# Walletv3.net
KiCad netlist of a schematic drawn in EAGLE
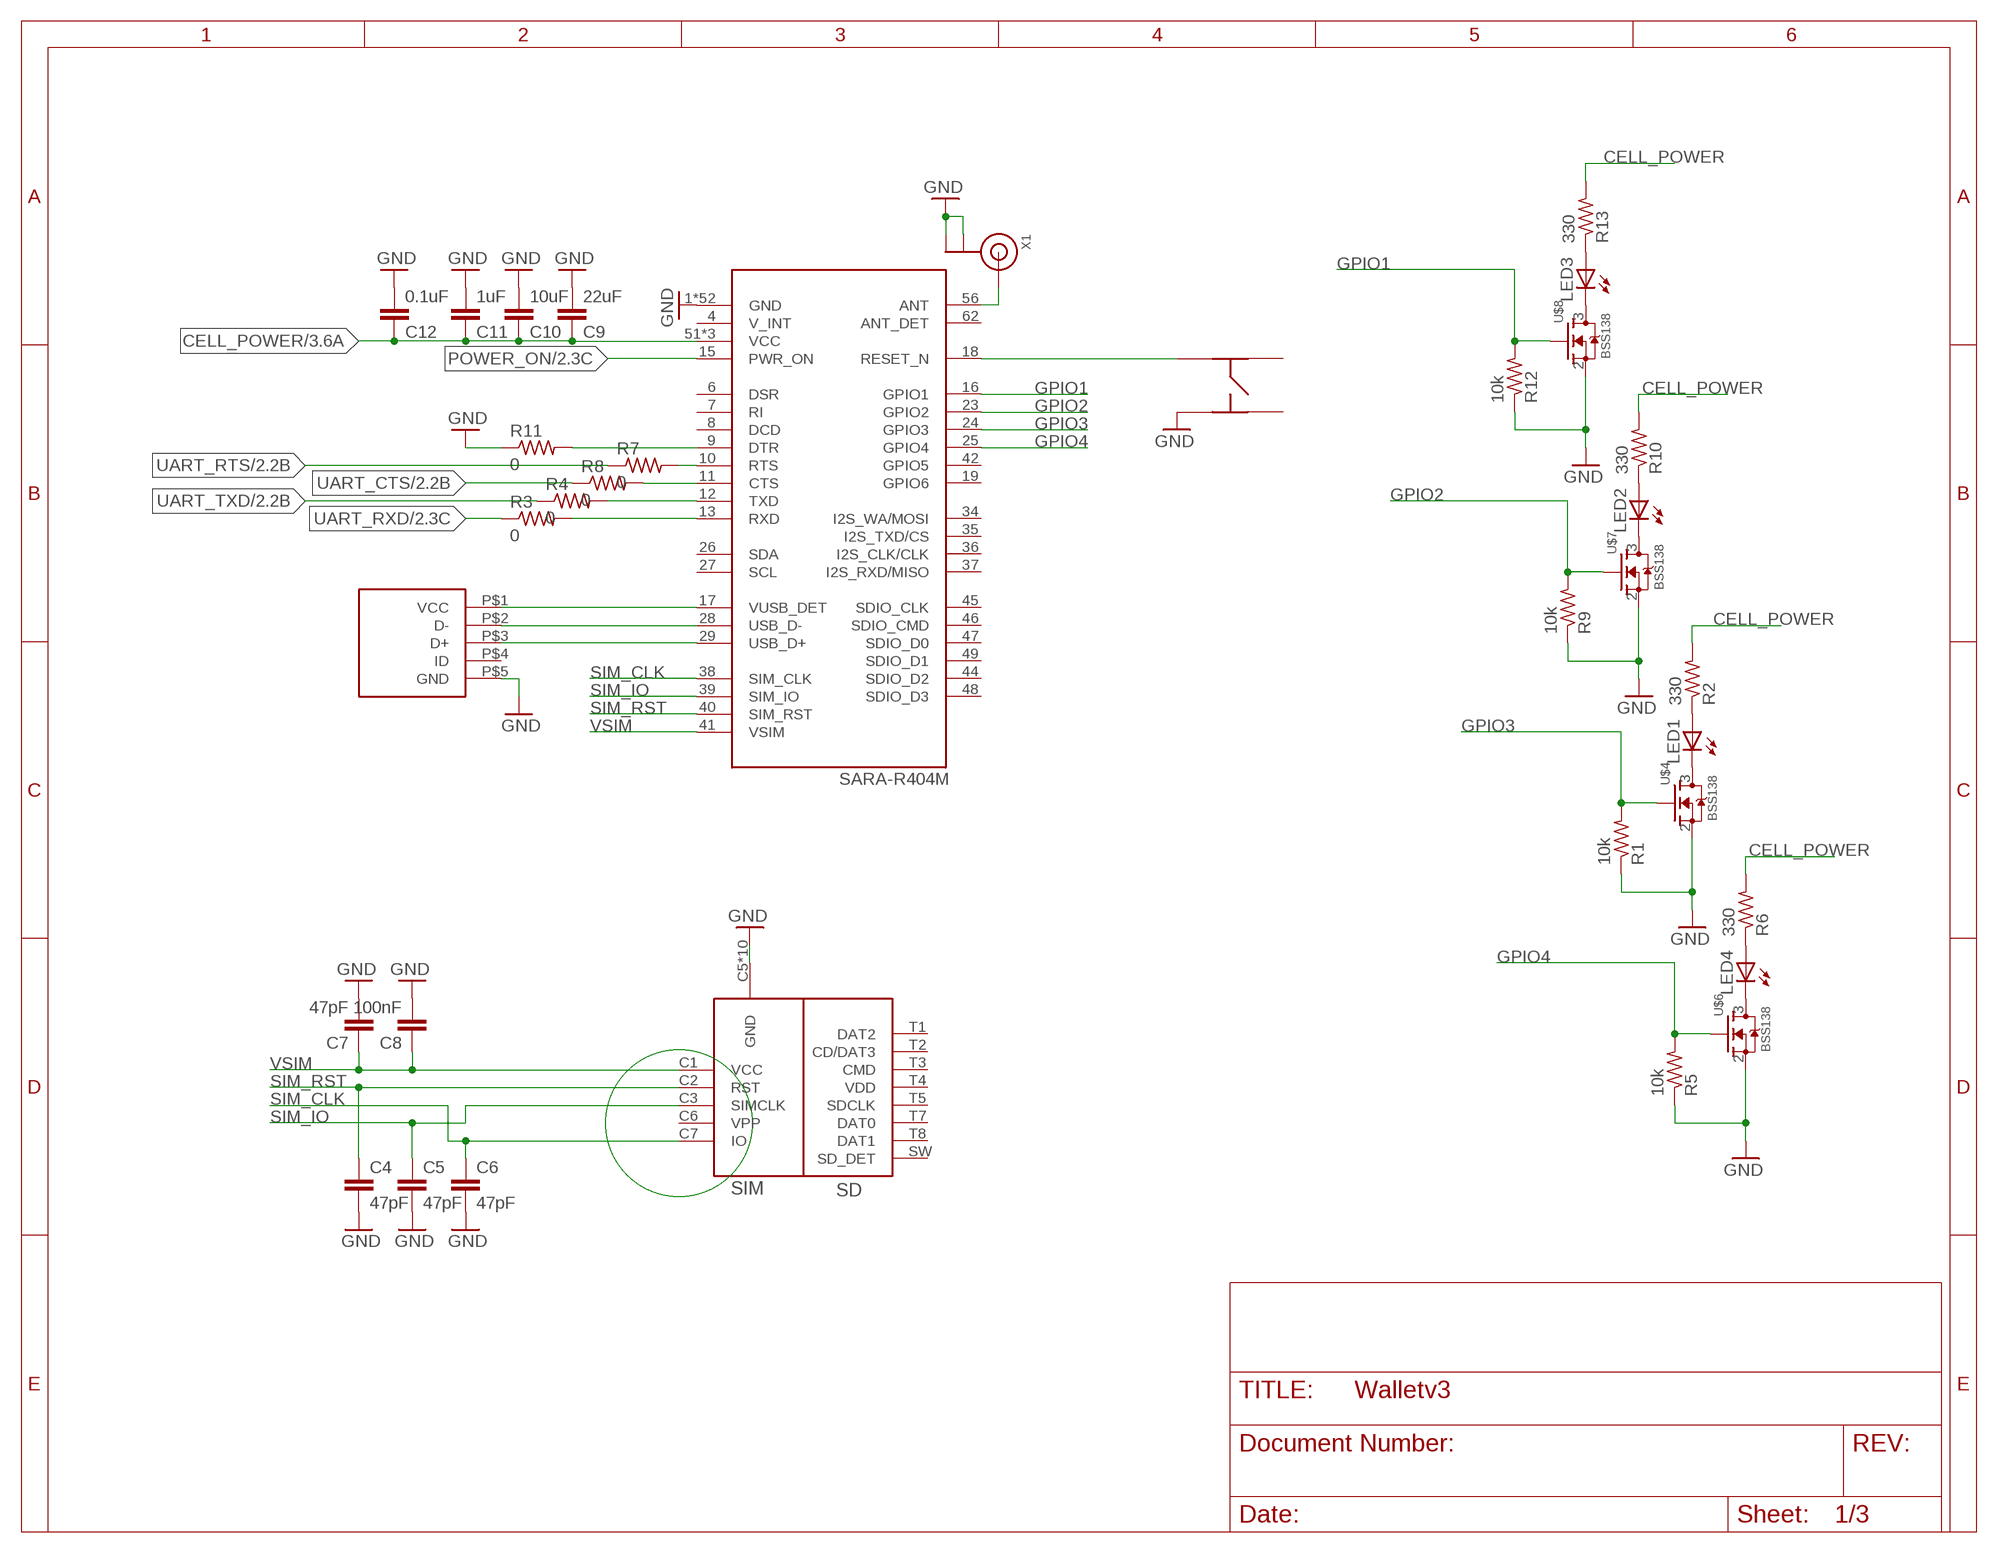
[diagram p0: schematic, sheet 1]
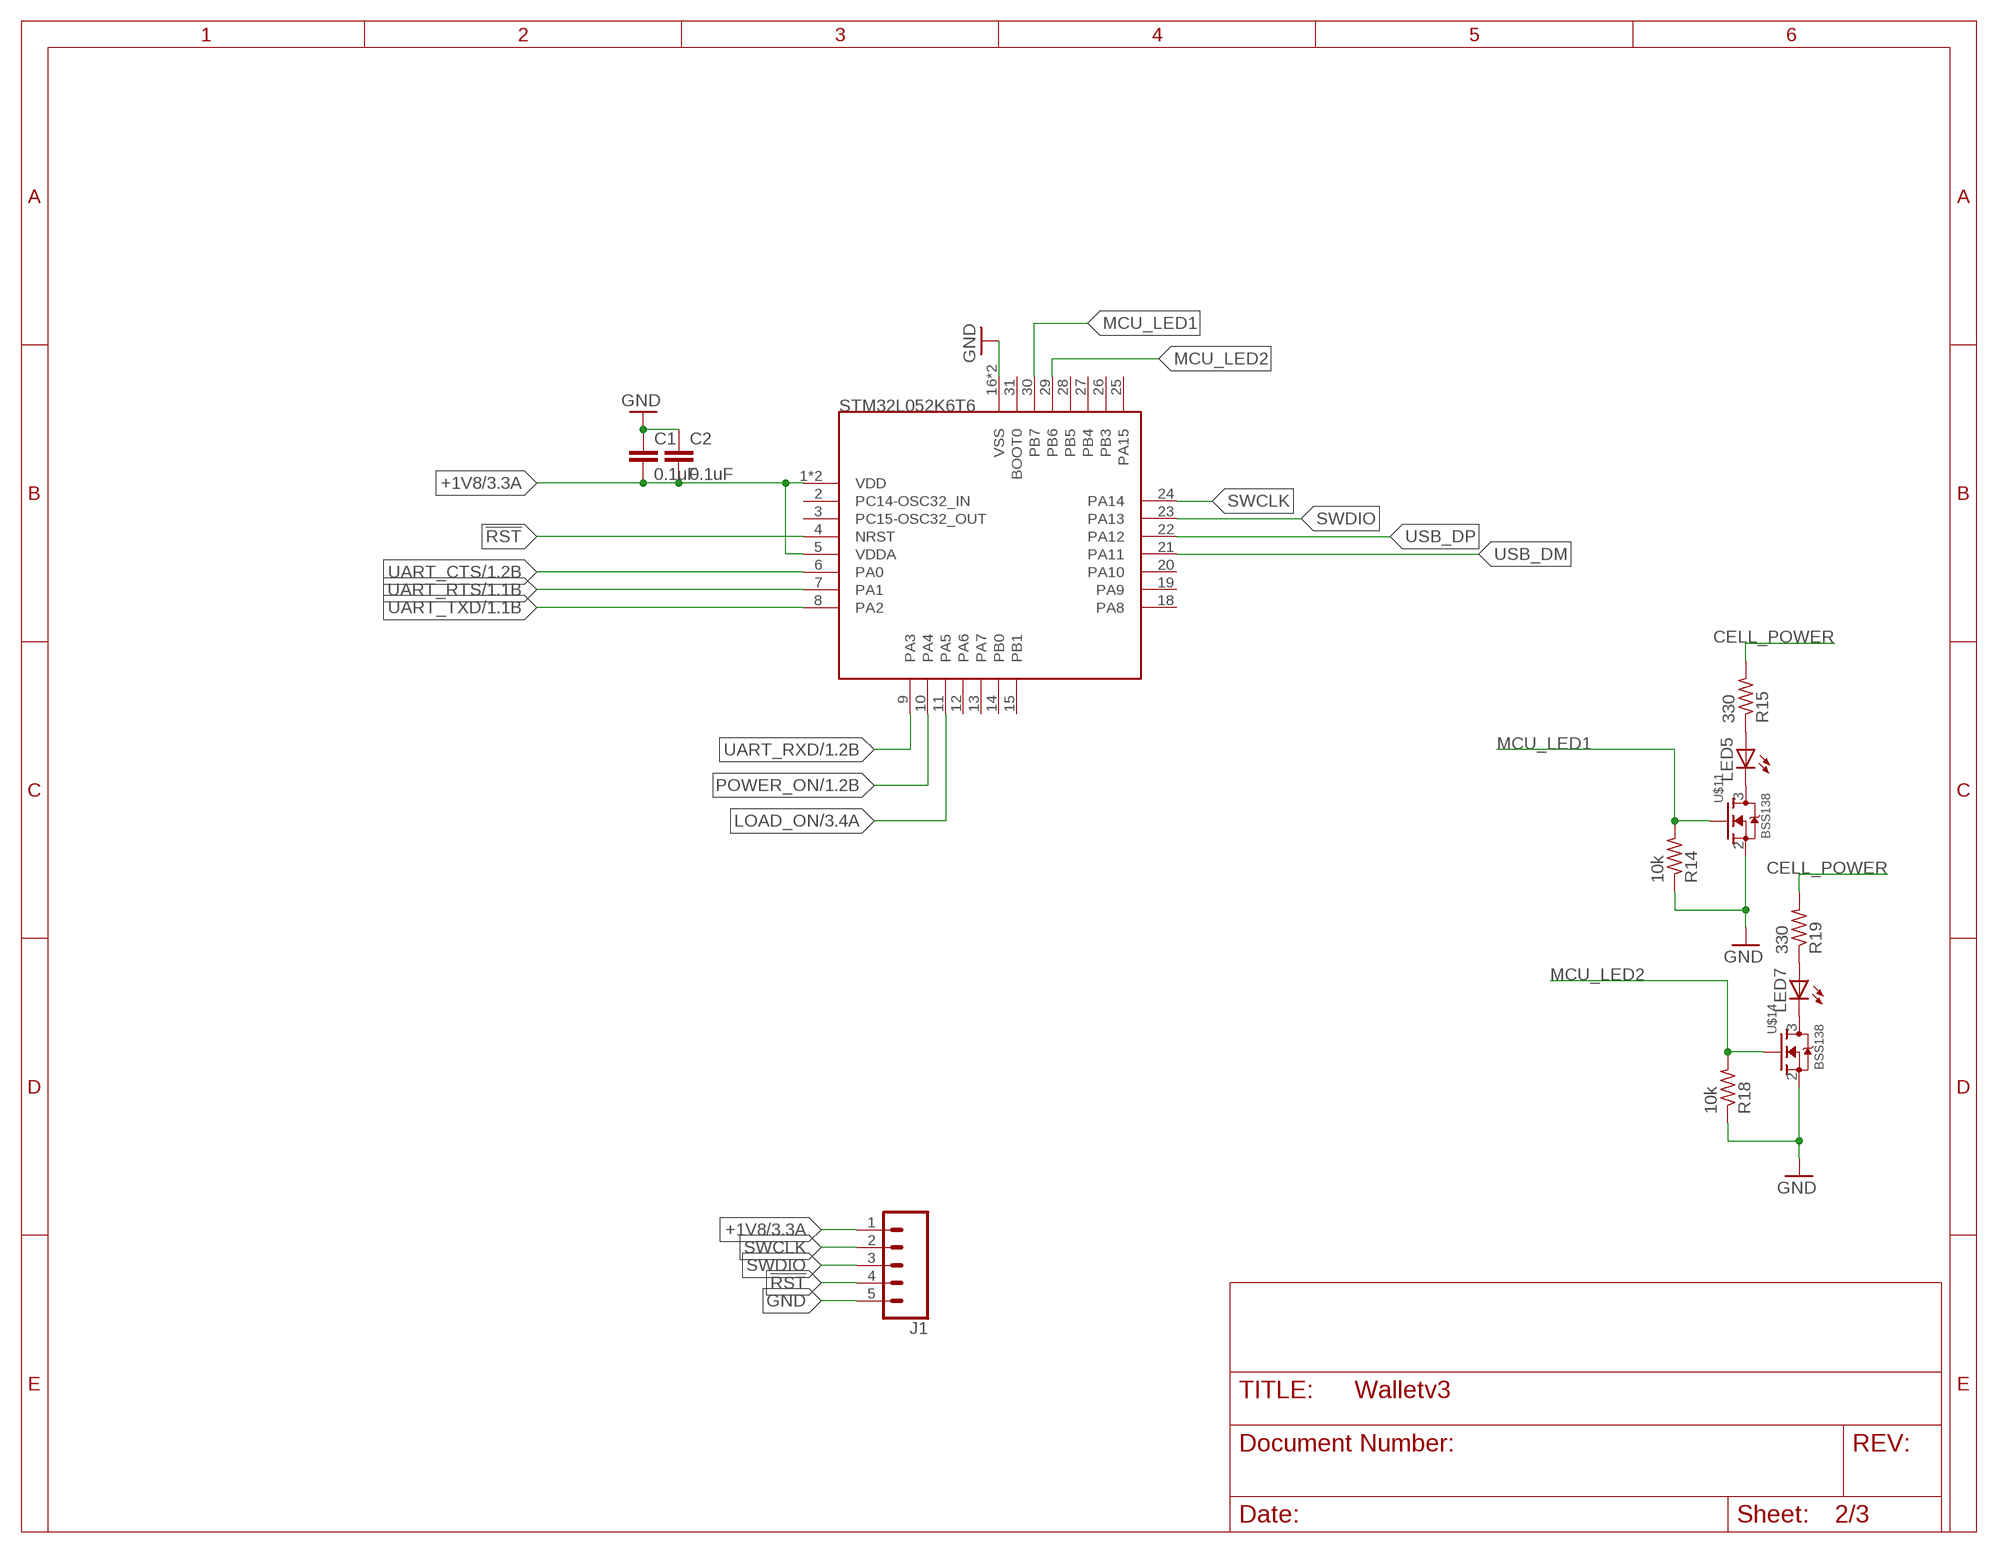
[diagram p1: schematic, sheet 2]
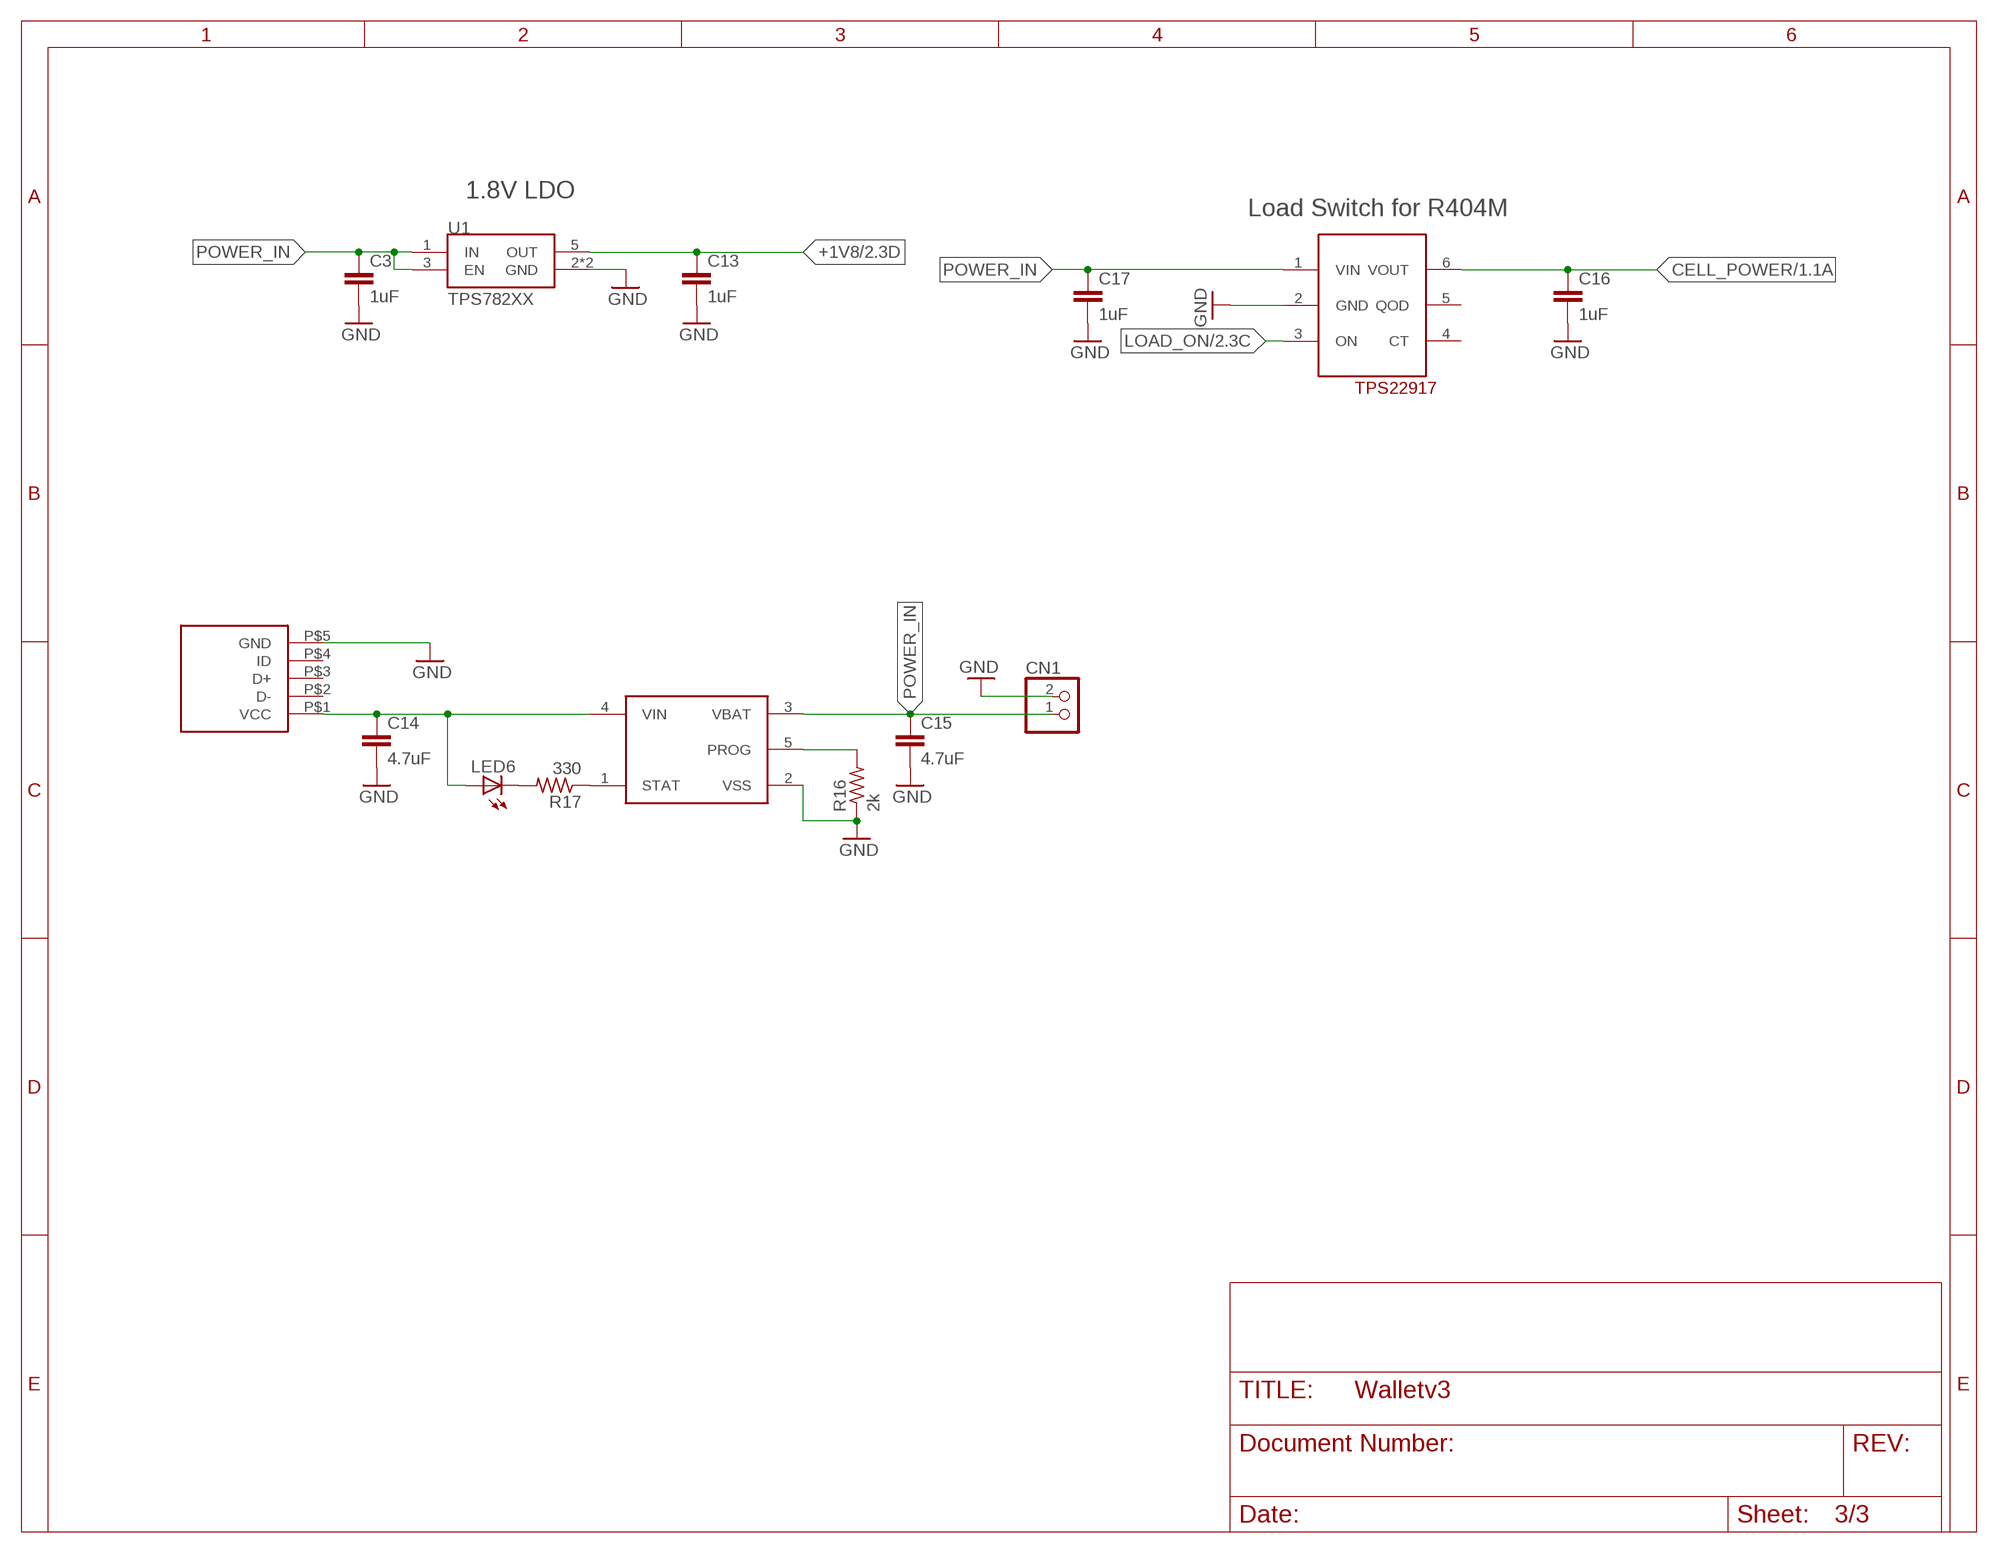
[diagram p2: schematic, sheet 3]

(export (version "E")
  (design (tool "Eeschema 10.0.6"))
  (components
    (comp (ref "C4")
      (value "47pF")
      (footprint "eagle-import:C0402")
      (libsource (lib "eagle-import") (part "C-EUC0402"))
    )
    (comp (ref "C5")
      (value "47pF")
      (footprint "eagle-import:C0402")
      (libsource (lib "eagle-import") (part "C-EUC0402"))
    )
    (comp (ref "C6")
      (value "47pF")
      (footprint "eagle-import:C0402")
      (libsource (lib "eagle-import") (part "C-EUC0402"))
    )
    (comp (ref "C7")
      (value "47pF")
      (footprint "eagle-import:C0402")
      (libsource (lib "eagle-import") (part "C-EUC0402"))
    )
    (comp (ref "C8")
      (value "100nF")
      (footprint "eagle-import:C0402")
      (libsource (lib "eagle-import") (part "C-EUC0402"))
    )
    (comp (ref "C9")
      (value "22uF")
      (footprint "eagle-import:C0805")
      (libsource (lib "eagle-import") (part "C-EUC0805"))
    )
    (comp (ref "C10")
      (value "10uF")
      (footprint "eagle-import:C0603")
      (libsource (lib "eagle-import") (part "C-EUC0603"))
    )
    (comp (ref "C11")
      (value "1uF")
      (footprint "eagle-import:C0402")
      (libsource (lib "eagle-import") (part "C-EUC0402"))
    )
    (comp (ref "C12")
      (value "0.1uF")
      (footprint "eagle-import:C0402")
      (libsource (lib "eagle-import") (part "C-EUC0402"))
    )
    (comp (ref "LED1")
      (value "LEDCHIPLED_0603")
      (footprint "eagle-import:CHIPLED_0603")
      (libsource (lib "eagle-import") (part "LEDCHIPLED_0603"))
    )
    (comp (ref "LED2")
      (value "LEDCHIPLED_0603")
      (footprint "eagle-import:CHIPLED_0603")
      (libsource (lib "eagle-import") (part "LEDCHIPLED_0603"))
    )
    (comp (ref "LED3")
      (value "LEDCHIPLED_0603")
      (footprint "eagle-import:CHIPLED_0603")
      (libsource (lib "eagle-import") (part "LEDCHIPLED_0603"))
    )
    (comp (ref "LED4")
      (value "LEDCHIPLED_0603")
      (footprint "eagle-import:CHIPLED_0603")
      (libsource (lib "eagle-import") (part "LEDCHIPLED_0603"))
    )
    (comp (ref "R1")
      (value "10k")
      (footprint "eagle-import:R0402")
      (libsource (lib "eagle-import") (part "R-US_R0402"))
    )
    (comp (ref "R2")
      (value "330")
      (footprint "eagle-import:R0402")
      (libsource (lib "eagle-import") (part "R-US_R0402"))
    )
    (comp (ref "R3")
      (value "0")
      (footprint "eagle-import:R0402")
      (libsource (lib "eagle-import") (part "R-US_R0402"))
    )
    (comp (ref "R4")
      (value "0")
      (footprint "eagle-import:R0402")
      (libsource (lib "eagle-import") (part "R-US_R0402"))
    )
    (comp (ref "R5")
      (value "10k")
      (footprint "eagle-import:R0402")
      (libsource (lib "eagle-import") (part "R-US_R0402"))
    )
    (comp (ref "R6")
      (value "330")
      (footprint "eagle-import:R0402")
      (libsource (lib "eagle-import") (part "R-US_R0402"))
    )
    (comp (ref "R7")
      (value "0")
      (footprint "eagle-import:R0402")
      (libsource (lib "eagle-import") (part "R-US_R0402"))
    )
    (comp (ref "R8")
      (value "0")
      (footprint "eagle-import:R0402")
      (libsource (lib "eagle-import") (part "R-US_R0402"))
    )
    (comp (ref "R9")
      (value "10k")
      (footprint "eagle-import:R0402")
      (libsource (lib "eagle-import") (part "R-US_R0402"))
    )
    (comp (ref "R10")
      (value "330")
      (footprint "eagle-import:R0402")
      (libsource (lib "eagle-import") (part "R-US_R0402"))
    )
    (comp (ref "R11")
      (value "0")
      (footprint "eagle-import:R0402")
      (libsource (lib "eagle-import") (part "R-US_R0402"))
    )
    (comp (ref "R12")
      (value "10k")
      (footprint "eagle-import:R0402")
      (libsource (lib "eagle-import") (part "R-US_R0402"))
    )
    (comp (ref "R13")
      (value "330")
      (footprint "eagle-import:R0402")
      (libsource (lib "eagle-import") (part "R-US_R0402"))
    )
    (comp (ref "U$2")
      (value "SIM_SD_MOLEX")
      (footprint "eagle-import:SIM_SD_MOLEX")
      (libsource (lib "eagle-import") (part "SIM_SD_MOLEX"))
    )
    (comp (ref "U$3")
      (value "SARA-R404M")
      (footprint "eagle-import:SARA-R404M")
      (libsource (lib "eagle-import") (part "SARA-R404M"))
    )
    (comp (ref "U$4")
      (value "BSS138")
      (footprint "eagle-import:SOT23-3")
      (libsource (lib "eagle-import") (part "BSS138"))
    )
    (comp (ref "U$5")
      (value "MICRO_USB")
      (footprint "eagle-import:MOLEX_USB")
      (libsource (lib "eagle-import") (part "Charles_104873_MICRO_USB"))
    )
    (comp (ref "U$6")
      (value "BSS138")
      (footprint "eagle-import:SOT23-3")
      (libsource (lib "eagle-import") (part "BSS138"))
    )
    (comp (ref "U$7")
      (value "BSS138")
      (footprint "eagle-import:SOT23-3")
      (libsource (lib "eagle-import") (part "BSS138"))
    )
    (comp (ref "U$8")
      (value "BSS138")
      (footprint "eagle-import:SOT23-3")
      (libsource (lib "eagle-import") (part "BSS138"))
    )
    (comp (ref "U$9")
      (value "KMR731NG")
      (footprint "eagle-import:KMR731NG")
      (libsource (lib "eagle-import") (part "KMR731NG"))
    )
    (comp (ref "X1")
      (value "ANTENNA_U.FL")
      (footprint "eagle-import:U.FL")
      (libsource (lib "eagle-import") (part "ANTENNA_U.FL"))
    )
    (comp (ref "C1")
      (value "0.1uF")
      (footprint "eagle-import:C0402")
      (libsource (lib "eagle-import") (part "C-EUC0402"))
    )
    (comp (ref "C2")
      (value "0.1uF")
      (footprint "eagle-import:C0402")
      (libsource (lib "eagle-import") (part "C-EUC0402"))
    )
    (comp (ref "J1")
      (value "CONN_05")
      (footprint "eagle-import:1X05")
      (libsource (lib "eagle-import") (part "CONN_05"))
    )
    (comp (ref "LED5")
      (value "LEDCHIPLED_0603")
      (footprint "eagle-import:CHIPLED_0603")
      (libsource (lib "eagle-import") (part "LEDCHIPLED_0603"))
    )
    (comp (ref "LED7")
      (value "LEDCHIPLED_0603")
      (footprint "eagle-import:CHIPLED_0603")
      (libsource (lib "eagle-import") (part "LEDCHIPLED_0603"))
    )
    (comp (ref "R14")
      (value "10k")
      (footprint "eagle-import:R0402")
      (libsource (lib "eagle-import") (part "R-US_R0402"))
    )
    (comp (ref "R15")
      (value "330")
      (footprint "eagle-import:R0402")
      (libsource (lib "eagle-import") (part "R-US_R0402"))
    )
    (comp (ref "R18")
      (value "10k")
      (footprint "eagle-import:R0402")
      (libsource (lib "eagle-import") (part "R-US_R0402"))
    )
    (comp (ref "R19")
      (value "330")
      (footprint "eagle-import:R0402")
      (libsource (lib "eagle-import") (part "R-US_R0402"))
    )
    (comp (ref "U$1")
      (value "STM32L052K6T6LQFP32-7X7")
      (footprint "eagle-import:QFP80P900X900X160-32")
      (libsource (lib "eagle-import") (part "STM32L052K6T6LQFP32-7X7"))
    )
    (comp (ref "U$11")
      (value "BSS138")
      (footprint "eagle-import:SOT23-3")
      (libsource (lib "eagle-import") (part "BSS138"))
    )
    (comp (ref "U$14")
      (value "BSS138")
      (footprint "eagle-import:SOT23-3")
      (libsource (lib "eagle-import") (part "BSS138"))
    )
    (comp (ref "C3")
      (value "1uF")
      (footprint "eagle-import:C0402")
      (libsource (lib "eagle-import") (part "C-EUC0402"))
    )
    (comp (ref "C13")
      (value "1uF")
      (footprint "eagle-import:C0402")
      (libsource (lib "eagle-import") (part "C-EUC0402"))
    )
    (comp (ref "C14")
      (value "4.7uF")
      (footprint "eagle-import:C0603")
      (libsource (lib "eagle-import") (part "C-EUC0603"))
    )
    (comp (ref "C15")
      (value "4.7uF")
      (footprint "eagle-import:C0603")
      (libsource (lib "eagle-import") (part "C-EUC0603"))
    )
    (comp (ref "C16")
      (value "1uF")
      (footprint "eagle-import:C0402")
      (libsource (lib "eagle-import") (part "C-EUC0402"))
    )
    (comp (ref "C17")
      (value "1uF")
      (footprint "eagle-import:C0402")
      (libsource (lib "eagle-import") (part "C-EUC0402"))
    )
    (comp (ref "CN1")
      (value "JST_2PIN-SMT-RA")
      (footprint "eagle-import:JST-PH-2-SMT-RA")
      (libsource (lib "eagle-import") (part "JST_2PIN-SMT-RA"))
    )
    (comp (ref "LED6")
      (value "LEDCHIP-LED0603")
      (footprint "eagle-import:CHIP-LED0603")
      (libsource (lib "eagle-import") (part "LEDCHIP-LED0603"))
    )
    (comp (ref "R16")
      (value "2k")
      (footprint "eagle-import:R0402")
      (libsource (lib "eagle-import") (part "R-US_R0402"))
    )
    (comp (ref "R17")
      (value "330")
      (footprint "eagle-import:R0402")
      (libsource (lib "eagle-import") (part "R-US_R0402"))
    )
    (comp (ref "U$10")
      (value "TPS22917")
      (footprint "eagle-import:SOT23-6")
      (libsource (lib "eagle-import") (part "TPS22917"))
    )
    (comp (ref "U$12")
      (value "MICRO_USB")
      (footprint "eagle-import:MOLEX_USB")
      (libsource (lib "eagle-import") (part "MICRO_USB"))
    )
    (comp (ref "U$13")
      (value "MCP73831")
      (footprint "eagle-import:SOT23-5L")
      (libsource (lib "eagle-import") (part "MCP73831"))
    )
    (comp (ref "U1")
      (value "TPS782XX")
      (footprint "eagle-import:SOT23-5L")
      (libsource (lib "eagle-import") (part "TPS782XX"))
    )
  )
  (nets
    (net (code "1") (name "+1V8") (class "Default")
      (node (ref "C1") (pin "2") (pinfunction "2_2") (pintype "passive"))
      (node (ref "C13") (pin "1") (pinfunction "1_1") (pintype "passive"))
      (node (ref "C2") (pin "2") (pinfunction "2_2") (pintype "passive"))
      (node (ref "J1") (pin "1") (pinfunction "1_1") (pintype "passive"))
      (node (ref "U$1") (pin "1") (pinfunction "VDD_1") (pintype "bidirectional"))
      (node (ref "U$1") (pin "17") (pinfunction "VDD_17") (pintype "bidirectional"))
      (node (ref "U$1") (pin "5") (pinfunction "VDDA_5") (pintype "bidirectional"))
      (node (ref "U1") (pin "5") (pinfunction "OUT_5") (pintype "bidirectional"))
    )
    (net (code "2") (name "CELL_POWER") (class "Default")
      (node (ref "C10") (pin "1") (pinfunction "1_1") (pintype "passive"))
      (node (ref "C11") (pin "1") (pinfunction "1_1") (pintype "passive"))
      (node (ref "C12") (pin "1") (pinfunction "1_1") (pintype "passive"))
      (node (ref "C16") (pin "1") (pinfunction "1_1") (pintype "passive"))
      (node (ref "C9") (pin "1") (pinfunction "1_1") (pintype "passive"))
      (node (ref "R10") (pin "2") (pinfunction "2_2") (pintype "passive"))
      (node (ref "R13") (pin "2") (pinfunction "2_2") (pintype "passive"))
      (node (ref "R15") (pin "2") (pinfunction "2_2") (pintype "passive"))
      (node (ref "R19") (pin "2") (pinfunction "2_2") (pintype "passive"))
      (node (ref "R2") (pin "2") (pinfunction "2_2") (pintype "passive"))
      (node (ref "R6") (pin "2") (pinfunction "2_2") (pintype "passive"))
      (node (ref "U$10") (pin "6") (pinfunction "VOUT_6") (pintype "bidirectional"))
      (node (ref "U$3") (pin "51") (pinfunction "VCC_51") (pintype "bidirectional"))
      (node (ref "U$3") (pin "52") (pinfunction "VCC_52") (pintype "bidirectional"))
      (node (ref "U$3") (pin "53") (pinfunction "VCC_53") (pintype "bidirectional"))
    )
    (net (code "3") (name "GND") (class "Default")
      (node (ref "C1") (pin "1") (pinfunction "1_1") (pintype "passive"))
      (node (ref "C10") (pin "2") (pinfunction "2_2") (pintype "passive"))
      (node (ref "C11") (pin "2") (pinfunction "2_2") (pintype "passive"))
      (node (ref "C12") (pin "2") (pinfunction "2_2") (pintype "passive"))
      (node (ref "C13") (pin "2") (pinfunction "2_2") (pintype "passive"))
      (node (ref "C14") (pin "2") (pinfunction "2_2") (pintype "passive"))
      (node (ref "C15") (pin "2") (pinfunction "2_2") (pintype "passive"))
      (node (ref "C16") (pin "2") (pinfunction "2_2") (pintype "passive"))
      (node (ref "C17") (pin "2") (pinfunction "2_2") (pintype "passive"))
      (node (ref "C2") (pin "1") (pinfunction "1_1") (pintype "passive"))
      (node (ref "C3") (pin "2") (pinfunction "2_2") (pintype "passive"))
      (node (ref "C4") (pin "2") (pinfunction "2_2") (pintype "passive"))
      (node (ref "C5") (pin "2") (pinfunction "2_2") (pintype "passive"))
      (node (ref "C6") (pin "2") (pinfunction "2_2") (pintype "passive"))
      (node (ref "C7") (pin "2") (pinfunction "2_2") (pintype "passive"))
      (node (ref "C8") (pin "2") (pinfunction "2_2") (pintype "passive"))
      (node (ref "C9") (pin "2") (pinfunction "2_2") (pintype "passive"))
      (node (ref "CN1") (pin "2") (pinfunction "1_2") (pintype "passive"))
      (node (ref "J1") (pin "5") (pinfunction "5_5") (pintype "passive"))
      (node (ref "R1") (pin "1") (pinfunction "1_1") (pintype "passive"))
      (node (ref "R11") (pin "1") (pinfunction "1_1") (pintype "passive"))
      (node (ref "R12") (pin "1") (pinfunction "1_1") (pintype "passive"))
      (node (ref "R14") (pin "1") (pinfunction "1_1") (pintype "passive"))
      (node (ref "R16") (pin "1") (pinfunction "1_1") (pintype "passive"))
      (node (ref "R18") (pin "1") (pinfunction "1_1") (pintype "passive"))
      (node (ref "R5") (pin "1") (pinfunction "1_1") (pintype "passive"))
      (node (ref "R9") (pin "1") (pinfunction "1_1") (pintype "passive"))
      (node (ref "U$1") (pin "16") (pinfunction "VSS_16") (pintype "bidirectional"))
      (node (ref "U$1") (pin "32") (pinfunction "VSS_32") (pintype "bidirectional"))
      (node (ref "U$10") (pin "2") (pinfunction "GND_2") (pintype "bidirectional"))
      (node (ref "U$11") (pin "2") (pinfunction "S_2") (pintype "bidirectional"))
      (node (ref "U$12") (pin "P$5") (pinfunction "GND_P$5") (pintype "bidirectional"))
      (node (ref "U$13") (pin "2") (pinfunction "VSS_2") (pintype "bidirectional"))
      (node (ref "U$14") (pin "2") (pinfunction "S_2") (pintype "bidirectional"))
      (node (ref "U$2") (pin "C5") (pinfunction "GND_C5") (pintype "bidirectional"))
      (node (ref "U$2") (pin "G1") (pinfunction "GND_G1") (pintype "bidirectional"))
      (node (ref "U$2") (pin "G2") (pinfunction "GND_G2") (pintype "bidirectional"))
      (node (ref "U$2") (pin "G3") (pinfunction "GND_G3") (pintype "bidirectional"))
      (node (ref "U$2") (pin "G4") (pinfunction "GND_G4") (pintype "bidirectional"))
      (node (ref "U$2") (pin "G5") (pinfunction "GND_G5") (pintype "bidirectional"))
      (node (ref "U$2") (pin "G6") (pinfunction "GND_G6") (pintype "bidirectional"))
      (node (ref "U$2") (pin "G7") (pinfunction "GND_G7") (pintype "bidirectional"))
      (node (ref "U$2") (pin "G8") (pinfunction "GND_G8") (pintype "bidirectional"))
      (node (ref "U$2") (pin "T6") (pinfunction "GND_T6") (pintype "bidirectional"))
      (node (ref "U$3") (pin "1") (pinfunction "GND_1") (pintype "bidirectional"))
      (node (ref "U$3") (pin "14") (pinfunction "GND_14") (pintype "bidirectional"))
      (node (ref "U$3") (pin "20") (pinfunction "GND_20") (pintype "bidirectional"))
      (node (ref "U$3") (pin "21") (pinfunction "GND_21") (pintype "bidirectional"))
      (node (ref "U$3") (pin "22") (pinfunction "GND_22") (pintype "bidirectional"))
      (node (ref "U$3") (pin "3") (pinfunction "GND_3") (pintype "bidirectional"))
      (node (ref "U$3") (pin "30") (pinfunction "GND_30") (pintype "bidirectional"))
      (node (ref "U$3") (pin "32") (pinfunction "GND_32") (pintype "bidirectional"))
      (node (ref "U$3") (pin "43") (pinfunction "GND_43") (pintype "bidirectional"))
      (node (ref "U$3") (pin "5") (pinfunction "GND_5") (pintype "bidirectional"))
      (node (ref "U$3") (pin "50") (pinfunction "GND_50") (pintype "bidirectional"))
      (node (ref "U$3") (pin "54") (pinfunction "GND_54") (pintype "bidirectional"))
      (node (ref "U$3") (pin "55") (pinfunction "GND_55") (pintype "bidirectional"))
      (node (ref "U$3") (pin "57") (pinfunction "GND_57") (pintype "bidirectional"))
      (node (ref "U$3") (pin "58") (pinfunction "GND_58") (pintype "bidirectional"))
      (node (ref "U$3") (pin "59") (pinfunction "GND_59") (pintype "bidirectional"))
      (node (ref "U$3") (pin "60") (pinfunction "GND_60") (pintype "bidirectional"))
      (node (ref "U$3") (pin "61") (pinfunction "GND_61") (pintype "bidirectional"))
      (node (ref "U$3") (pin "63") (pinfunction "GND_63") (pintype "bidirectional"))
      (node (ref "U$3") (pin "64") (pinfunction "GND_64") (pintype "bidirectional"))
      (node (ref "U$3") (pin "65") (pinfunction "GND_65") (pintype "bidirectional"))
      (node (ref "U$3") (pin "66") (pinfunction "GND_66") (pintype "bidirectional"))
      (node (ref "U$3") (pin "67") (pinfunction "GND_67") (pintype "bidirectional"))
      (node (ref "U$3") (pin "68") (pinfunction "GND_68") (pintype "bidirectional"))
      (node (ref "U$3") (pin "69") (pinfunction "GND_69") (pintype "bidirectional"))
      (node (ref "U$3") (pin "70") (pinfunction "GND_70") (pintype "bidirectional"))
      (node (ref "U$3") (pin "71") (pinfunction "GND_71") (pintype "bidirectional"))
      (node (ref "U$3") (pin "72") (pinfunction "GND_72") (pintype "bidirectional"))
      (node (ref "U$3") (pin "73") (pinfunction "GND_73") (pintype "bidirectional"))
      (node (ref "U$3") (pin "74") (pinfunction "GND_74") (pintype "bidirectional"))
      (node (ref "U$3") (pin "75") (pinfunction "GND_75") (pintype "bidirectional"))
      (node (ref "U$3") (pin "76") (pinfunction "GND_76") (pintype "bidirectional"))
      (node (ref "U$3") (pin "77") (pinfunction "GND_77") (pintype "bidirectional"))
      (node (ref "U$3") (pin "78") (pinfunction "GND_78") (pintype "bidirectional"))
      (node (ref "U$3") (pin "79") (pinfunction "GND_79") (pintype "bidirectional"))
      (node (ref "U$3") (pin "80") (pinfunction "GND_80") (pintype "bidirectional"))
      (node (ref "U$3") (pin "81") (pinfunction "GND_81") (pintype "bidirectional"))
      (node (ref "U$3") (pin "82") (pinfunction "GND_82") (pintype "bidirectional"))
      (node (ref "U$3") (pin "83") (pinfunction "GND_83") (pintype "bidirectional"))
      (node (ref "U$3") (pin "84") (pinfunction "GND_84") (pintype "bidirectional"))
      (node (ref "U$3") (pin "85") (pinfunction "GND_85") (pintype "bidirectional"))
      (node (ref "U$3") (pin "86") (pinfunction "GND_86") (pintype "bidirectional"))
      (node (ref "U$3") (pin "87") (pinfunction "GND_87") (pintype "bidirectional"))
      (node (ref "U$3") (pin "88") (pinfunction "GND_88") (pintype "bidirectional"))
      (node (ref "U$3") (pin "89") (pinfunction "GND_89") (pintype "bidirectional"))
      (node (ref "U$3") (pin "90") (pinfunction "GND_90") (pintype "bidirectional"))
      (node (ref "U$3") (pin "91") (pinfunction "GND_91") (pintype "bidirectional"))
      (node (ref "U$3") (pin "92") (pinfunction "GND_92") (pintype "bidirectional"))
      (node (ref "U$3") (pin "93") (pinfunction "GND_93") (pintype "bidirectional"))
      (node (ref "U$3") (pin "94") (pinfunction "GND_94") (pintype "bidirectional"))
      (node (ref "U$3") (pin "95") (pinfunction "GND_95") (pintype "bidirectional"))
      (node (ref "U$3") (pin "96") (pinfunction "GND_96") (pintype "bidirectional"))
      (node (ref "U$4") (pin "2") (pinfunction "S_2") (pintype "bidirectional"))
      (node (ref "U$5") (pin "P$5") (pinfunction "GND_P$5") (pintype "bidirectional"))
      (node (ref "U$6") (pin "2") (pinfunction "S_2") (pintype "bidirectional"))
      (node (ref "U$7") (pin "2") (pinfunction "S_2") (pintype "bidirectional"))
      (node (ref "U$8") (pin "2") (pinfunction "S_2") (pintype "bidirectional"))
      (node (ref "U$9") (pin "P$4") (pinfunction "P$4_P$4") (pintype "bidirectional"))
      (node (ref "U1") (pin "2") (pinfunction "GND_2") (pintype "bidirectional"))
      (node (ref "U1") (pin "4") (pinfunction "GND_4") (pintype "bidirectional"))
      (node (ref "X1") (pin "1") (pinfunction "GND_1") (pintype "passive"))
      (node (ref "X1") (pin "2") (pinfunction "GND_2") (pintype "passive"))
    )
    (net (code "4") (name "GPIO1") (class "Default")
      (node (ref "R12") (pin "2") (pinfunction "2_2") (pintype "passive"))
      (node (ref "U$3") (pin "16") (pinfunction "GPIO1_16") (pintype "bidirectional"))
      (node (ref "U$8") (pin "1") (pinfunction "G_1") (pintype "bidirectional"))
    )
    (net (code "5") (name "GPIO2") (class "Default")
      (node (ref "R9") (pin "2") (pinfunction "2_2") (pintype "passive"))
      (node (ref "U$3") (pin "23") (pinfunction "GPIO2_23") (pintype "bidirectional"))
      (node (ref "U$7") (pin "1") (pinfunction "G_1") (pintype "bidirectional"))
    )
    (net (code "6") (name "GPIO3") (class "Default")
      (node (ref "R1") (pin "2") (pinfunction "2_2") (pintype "passive"))
      (node (ref "U$3") (pin "24") (pinfunction "GPIO3_24") (pintype "bidirectional"))
      (node (ref "U$4") (pin "1") (pinfunction "G_1") (pintype "bidirectional"))
    )
    (net (code "7") (name "GPIO4") (class "Default")
      (node (ref "R5") (pin "2") (pinfunction "2_2") (pintype "passive"))
      (node (ref "U$3") (pin "25") (pinfunction "GPIO4_25") (pintype "bidirectional"))
      (node (ref "U$6") (pin "1") (pinfunction "G_1") (pintype "bidirectional"))
    )
    (net (code "8") (name "LOAD_ON") (class "Default")
      (node (ref "U$1") (pin "11") (pinfunction "PA5_11") (pintype "bidirectional"))
      (node (ref "U$10") (pin "3") (pinfunction "ON_3") (pintype "bidirectional"))
    )
    (net (code "9") (name "MCU_LED1") (class "Default")
      (node (ref "R14") (pin "2") (pinfunction "2_2") (pintype "passive"))
      (node (ref "U$1") (pin "30") (pinfunction "PB7_30") (pintype "bidirectional"))
      (node (ref "U$11") (pin "1") (pinfunction "G_1") (pintype "bidirectional"))
    )
    (net (code "10") (name "MCU_LED2") (class "Default")
      (node (ref "R18") (pin "2") (pinfunction "2_2") (pintype "passive"))
      (node (ref "U$1") (pin "29") (pinfunction "PB6_29") (pintype "bidirectional"))
      (node (ref "U$14") (pin "1") (pinfunction "G_1") (pintype "bidirectional"))
    )
    (net (code "11") (name "Net-(LED1-PadA)") (class "Default")
      (node (ref "LED1") (pin "A") (pinfunction "A_A") (pintype "passive"))
      (node (ref "R2") (pin "1") (pinfunction "1_1") (pintype "passive"))
    )
    (net (code "12") (name "Net-(LED2-PadA)") (class "Default")
      (node (ref "LED2") (pin "A") (pinfunction "A_A") (pintype "passive"))
      (node (ref "R10") (pin "1") (pinfunction "1_1") (pintype "passive"))
    )
    (net (code "13") (name "Net-(LED3-PadA)") (class "Default")
      (node (ref "LED3") (pin "A") (pinfunction "A_A") (pintype "passive"))
      (node (ref "R13") (pin "1") (pinfunction "1_1") (pintype "passive"))
    )
    (net (code "14") (name "Net-(LED4-PadA)") (class "Default")
      (node (ref "LED4") (pin "A") (pinfunction "A_A") (pintype "passive"))
      (node (ref "R6") (pin "1") (pinfunction "1_1") (pintype "passive"))
    )
    (net (code "15") (name "Net-(LED5-PadA)") (class "Default")
      (node (ref "LED5") (pin "A") (pinfunction "A_A") (pintype "passive"))
      (node (ref "R15") (pin "1") (pinfunction "1_1") (pintype "passive"))
    )
    (net (code "16") (name "Net-(LED6-PadC)") (class "Default")
      (node (ref "LED6") (pin "C") (pinfunction "C_C") (pintype "passive"))
      (node (ref "R17") (pin "2") (pinfunction "2_2") (pintype "passive"))
    )
    (net (code "17") (name "Net-(LED7-PadA)") (class "Default")
      (node (ref "LED7") (pin "A") (pinfunction "A_A") (pintype "passive"))
      (node (ref "R19") (pin "1") (pinfunction "1_1") (pintype "passive"))
    )
    (net (code "18") (name "Net-(U$3-ANT)") (class "Default")
      (node (ref "U$3") (pin "56") (pinfunction "ANT_56") (pintype "bidirectional"))
      (node (ref "X1") (pin "3") (pinfunction "SIGNAL_3") (pintype "passive"))
    )
    (net (code "19") (name "Net-(U$3-CTS)") (class "Default")
      (node (ref "R8") (pin "2") (pinfunction "2_2") (pintype "passive"))
      (node (ref "U$3") (pin "11") (pinfunction "CTS_11") (pintype "bidirectional"))
    )
    (net (code "20") (name "Net-(U$3-DTR)") (class "Default")
      (node (ref "R11") (pin "2") (pinfunction "2_2") (pintype "passive"))
      (node (ref "U$3") (pin "9") (pinfunction "DTR_9") (pintype "bidirectional"))
    )
    (net (code "21") (name "Net-(U$3-RESET_N)") (class "Default")
      (node (ref "U$3") (pin "18") (pinfunction "RESET_N_18") (pintype "bidirectional"))
      (node (ref "U$9") (pin "P$1") (pinfunction "P$1_P$1") (pintype "bidirectional"))
    )
    (net (code "22") (name "Net-(U$3-RTS)") (class "Default")
      (node (ref "R7") (pin "2") (pinfunction "2_2") (pintype "passive"))
      (node (ref "U$3") (pin "10") (pinfunction "RTS_10") (pintype "bidirectional"))
    )
    (net (code "23") (name "Net-(U$3-RXD)") (class "Default")
      (node (ref "R3") (pin "2") (pinfunction "2_2") (pintype "passive"))
      (node (ref "U$3") (pin "13") (pinfunction "RXD_13") (pintype "bidirectional"))
    )
    (net (code "24") (name "Net-(U$3-TXD)") (class "Default")
      (node (ref "R4") (pin "2") (pinfunction "2_2") (pintype "passive"))
      (node (ref "U$3") (pin "12") (pinfunction "TXD_12") (pintype "bidirectional"))
    )
    (net (code "25") (name "Net-(U$3-USB_D+)") (class "Default")
      (node (ref "U$3") (pin "29") (pinfunction "USB_D+_29") (pintype "bidirectional"))
      (node (ref "U$5") (pin "P$3") (pinfunction "D+_P$3") (pintype "bidirectional"))
    )
    (net (code "26") (name "Net-(U$3-USB_D-)") (class "Default")
      (node (ref "U$3") (pin "28") (pinfunction "USB_D-_28") (pintype "bidirectional"))
      (node (ref "U$5") (pin "P$2") (pinfunction "D-_P$2") (pintype "bidirectional"))
    )
    (net (code "27") (name "Net-(U$3-VUSB_DET)") (class "Default")
      (node (ref "U$3") (pin "17") (pinfunction "VUSB_DET_17") (pintype "bidirectional"))
      (node (ref "U$5") (pin "P$1") (pinfunction "VCC_P$1") (pintype "bidirectional"))
    )
    (net (code "28") (name "Net-(U$4-D)") (class "Default")
      (node (ref "LED1") (pin "C") (pinfunction "C_C") (pintype "passive"))
      (node (ref "U$4") (pin "3") (pinfunction "D_3") (pintype "bidirectional"))
    )
    (net (code "29") (name "Net-(U$6-D)") (class "Default")
      (node (ref "LED4") (pin "C") (pinfunction "C_C") (pintype "passive"))
      (node (ref "U$6") (pin "3") (pinfunction "D_3") (pintype "bidirectional"))
    )
    (net (code "30") (name "Net-(U$7-D)") (class "Default")
      (node (ref "LED2") (pin "C") (pinfunction "C_C") (pintype "passive"))
      (node (ref "U$7") (pin "3") (pinfunction "D_3") (pintype "bidirectional"))
    )
    (net (code "31") (name "Net-(U$8-D)") (class "Default")
      (node (ref "LED3") (pin "C") (pinfunction "C_C") (pintype "passive"))
      (node (ref "U$8") (pin "3") (pinfunction "D_3") (pintype "bidirectional"))
    )
    (net (code "32") (name "Net-(U$11-D)") (class "Default")
      (node (ref "LED5") (pin "C") (pinfunction "C_C") (pintype "passive"))
      (node (ref "U$11") (pin "3") (pinfunction "D_3") (pintype "bidirectional"))
    )
    (net (code "33") (name "Net-(U$12-VCC)") (class "Default")
      (node (ref "C14") (pin "1") (pinfunction "1_1") (pintype "passive"))
      (node (ref "LED6") (pin "A") (pinfunction "A_A") (pintype "passive"))
      (node (ref "U$12") (pin "P$1") (pinfunction "VCC_P$1") (pintype "bidirectional"))
      (node (ref "U$13") (pin "4") (pinfunction "VIN_4") (pintype "bidirectional"))
    )
    (net (code "34") (name "Net-(U$13-PROG)") (class "Default")
      (node (ref "R16") (pin "2") (pinfunction "2_2") (pintype "passive"))
      (node (ref "U$13") (pin "5") (pinfunction "PROG_5") (pintype "bidirectional"))
    )
    (net (code "35") (name "Net-(U$13-STAT)") (class "Default")
      (node (ref "R17") (pin "1") (pinfunction "1_1") (pintype "passive"))
      (node (ref "U$13") (pin "1") (pinfunction "STAT_1") (pintype "bidirectional"))
    )
    (net (code "36") (name "Net-(U$14-D)") (class "Default")
      (node (ref "LED7") (pin "C") (pinfunction "C_C") (pintype "passive"))
      (node (ref "U$14") (pin "3") (pinfunction "D_3") (pintype "bidirectional"))
    )
    (net (code "37") (name "POWER_IN") (class "Default")
      (node (ref "C15") (pin "1") (pinfunction "1_1") (pintype "passive"))
      (node (ref "C17") (pin "1") (pinfunction "1_1") (pintype "passive"))
      (node (ref "C3") (pin "1") (pinfunction "1_1") (pintype "passive"))
      (node (ref "CN1") (pin "1") (pinfunction "2_1") (pintype "passive"))
      (node (ref "U$10") (pin "1") (pinfunction "VIN_1") (pintype "bidirectional"))
      (node (ref "U$13") (pin "3") (pinfunction "VBAT_3") (pintype "bidirectional"))
      (node (ref "U1") (pin "1") (pinfunction "IN_1") (pintype "bidirectional"))
      (node (ref "U1") (pin "3") (pinfunction "EN_3") (pintype "bidirectional"))
    )
    (net (code "38") (name "POWER_ON") (class "Default")
      (node (ref "U$1") (pin "10") (pinfunction "PA4_10") (pintype "bidirectional"))
      (node (ref "U$3") (pin "15") (pinfunction "PWR_ON_15") (pintype "bidirectional"))
    )
    (net (code "39") (name "SIM_CLK") (class "Default")
      (node (ref "C6") (pin "1") (pinfunction "1_1") (pintype "passive"))
      (node (ref "U$2") (pin "C7") (pinfunction "IO_C7") (pintype "bidirectional"))
      (node (ref "U$3") (pin "38") (pinfunction "SIM_CLK_38") (pintype "bidirectional"))
    )
    (net (code "40") (name "SIM_IO") (class "Default")
      (node (ref "C5") (pin "1") (pinfunction "1_1") (pintype "passive"))
      (node (ref "U$2") (pin "C3") (pinfunction "SIMCLK_C3") (pintype "bidirectional"))
      (node (ref "U$3") (pin "39") (pinfunction "SIM_IO_39") (pintype "bidirectional"))
    )
    (net (code "41") (name "SIM_RST") (class "Default")
      (node (ref "C4") (pin "1") (pinfunction "1_1") (pintype "passive"))
      (node (ref "U$2") (pin "C2") (pinfunction "RST_C2") (pintype "bidirectional"))
      (node (ref "U$3") (pin "40") (pinfunction "SIM_RST_40") (pintype "bidirectional"))
    )
    (net (code "42") (name "SWCLK") (class "Default")
      (node (ref "J1") (pin "2") (pinfunction "2_2") (pintype "passive"))
      (node (ref "U$1") (pin "24") (pinfunction "PA14_24") (pintype "bidirectional"))
    )
    (net (code "43") (name "SWDIO") (class "Default")
      (node (ref "J1") (pin "3") (pinfunction "3_3") (pintype "passive"))
      (node (ref "U$1") (pin "23") (pinfunction "PA13_23") (pintype "bidirectional"))
    )
    (net (code "44") (name "UART_CTS") (class "Default")
      (node (ref "R8") (pin "1") (pinfunction "1_1") (pintype "passive"))
      (node (ref "U$1") (pin "6") (pinfunction "PA0_6") (pintype "bidirectional"))
    )
    (net (code "45") (name "UART_RTS") (class "Default")
      (node (ref "R7") (pin "1") (pinfunction "1_1") (pintype "passive"))
      (node (ref "U$1") (pin "7") (pinfunction "PA1_7") (pintype "bidirectional"))
    )
    (net (code "46") (name "UART_RXD") (class "Default")
      (node (ref "R3") (pin "1") (pinfunction "1_1") (pintype "passive"))
      (node (ref "U$1") (pin "9") (pinfunction "PA3_9") (pintype "bidirectional"))
    )
    (net (code "47") (name "UART_TXD") (class "Default")
      (node (ref "R4") (pin "1") (pinfunction "1_1") (pintype "passive"))
      (node (ref "U$1") (pin "8") (pinfunction "PA2_8") (pintype "bidirectional"))
    )
    (net (code "48") (name "USB_DM") (class "Default")
      (node (ref "U$1") (pin "21") (pinfunction "PA11_21") (pintype "bidirectional"))
    )
    (net (code "49") (name "USB_DP") (class "Default")
      (node (ref "U$1") (pin "22") (pinfunction "PA12_22") (pintype "bidirectional"))
    )
    (net (code "50") (name "VSIM") (class "Default")
      (node (ref "C7") (pin "1") (pinfunction "1_1") (pintype "passive"))
      (node (ref "C8") (pin "1") (pinfunction "1_1") (pintype "passive"))
      (node (ref "U$2") (pin "C1") (pinfunction "VCC_C1") (pintype "bidirectional"))
      (node (ref "U$3") (pin "41") (pinfunction "VSIM_41") (pintype "bidirectional"))
    )
    (net (code "51") (name "unconnected-(U$1-BOOT0-Pad31)") (class "Default")
      (node (ref "U$1") (pin "31") (pinfunction "BOOT0_31") (pintype "bidirectional"))
    )
    (net (code "52") (name "unconnected-(U$1-PA6-Pad12)") (class "Default")
      (node (ref "U$1") (pin "12") (pinfunction "PA6_12") (pintype "bidirectional"))
    )
    (net (code "53") (name "unconnected-(U$1-PA7-Pad13)") (class "Default")
      (node (ref "U$1") (pin "13") (pinfunction "PA7_13") (pintype "bidirectional"))
    )
    (net (code "54") (name "unconnected-(U$1-PA8-Pad18)") (class "Default")
      (node (ref "U$1") (pin "18") (pinfunction "PA8_18") (pintype "bidirectional"))
    )
    (net (code "55") (name "unconnected-(U$1-PA9-Pad19)") (class "Default")
      (node (ref "U$1") (pin "19") (pinfunction "PA9_19") (pintype "bidirectional"))
    )
    (net (code "56") (name "unconnected-(U$1-PA10-Pad20)") (class "Default")
      (node (ref "U$1") (pin "20") (pinfunction "PA10_20") (pintype "bidirectional"))
    )
    (net (code "57") (name "unconnected-(U$1-PA15-Pad25)") (class "Default")
      (node (ref "U$1") (pin "25") (pinfunction "PA15_25") (pintype "bidirectional"))
    )
    (net (code "58") (name "unconnected-(U$1-PB0-Pad14)") (class "Default")
      (node (ref "U$1") (pin "14") (pinfunction "PB0_14") (pintype "bidirectional"))
    )
    (net (code "59") (name "unconnected-(U$1-PB1-Pad15)") (class "Default")
      (node (ref "U$1") (pin "15") (pinfunction "PB1_15") (pintype "bidirectional"))
    )
    (net (code "60") (name "unconnected-(U$1-PB3-Pad26)") (class "Default")
      (node (ref "U$1") (pin "26") (pinfunction "PB3_26") (pintype "bidirectional"))
    )
    (net (code "61") (name "unconnected-(U$1-PB4-Pad27)") (class "Default")
      (node (ref "U$1") (pin "27") (pinfunction "PB4_27") (pintype "bidirectional"))
    )
    (net (code "62") (name "unconnected-(U$1-PB5-Pad28)") (class "Default")
      (node (ref "U$1") (pin "28") (pinfunction "PB5_28") (pintype "bidirectional"))
    )
    (net (code "63") (name "unconnected-(U$1-PC14-OSC32_IN-Pad2)") (class "Default")
      (node (ref "U$1") (pin "2") (pinfunction "PC14-OSC32_IN_2") (pintype "bidirectional"))
    )
    (net (code "64") (name "unconnected-(U$1-PC15-OSC32_OUT-Pad3)") (class "Default")
      (node (ref "U$1") (pin "3") (pinfunction "PC15-OSC32_OUT_3") (pintype "bidirectional"))
    )
    (net (code "65") (name "unconnected-(U$2-CD{slash}DAT3-PadT2)") (class "Default")
      (node (ref "U$2") (pin "T2") (pinfunction "CD/DAT3_T2") (pintype "bidirectional"))
    )
    (net (code "66") (name "unconnected-(U$2-CMD-PadT3)") (class "Default")
      (node (ref "U$2") (pin "T3") (pinfunction "CMD_T3") (pintype "bidirectional"))
    )
    (net (code "67") (name "unconnected-(U$2-DAT0-PadT7)") (class "Default")
      (node (ref "U$2") (pin "T7") (pinfunction "DAT0_T7") (pintype "bidirectional"))
    )
    (net (code "68") (name "unconnected-(U$2-DAT1-PadT8)") (class "Default")
      (node (ref "U$2") (pin "T8") (pinfunction "DAT1_T8") (pintype "bidirectional"))
    )
    (net (code "69") (name "unconnected-(U$2-DAT2-PadT1)") (class "Default")
      (node (ref "U$2") (pin "T1") (pinfunction "DAT2_T1") (pintype "bidirectional"))
    )
    (net (code "70") (name "unconnected-(U$2-SDCLK-PadT5)") (class "Default")
      (node (ref "U$2") (pin "T5") (pinfunction "SDCLK_T5") (pintype "bidirectional"))
    )
    (net (code "71") (name "unconnected-(U$2-SD_DET-PadSW)") (class "Default")
      (node (ref "U$2") (pin "SW") (pinfunction "SD_DET_SW") (pintype "bidirectional"))
    )
    (net (code "72") (name "unconnected-(U$2-VDD-PadT4)") (class "Default")
      (node (ref "U$2") (pin "T4") (pinfunction "VDD_T4") (pintype "bidirectional"))
    )
    (net (code "73") (name "unconnected-(U$2-VPP-PadC6)") (class "Default")
      (node (ref "U$2") (pin "C6") (pinfunction "VPP_C6") (pintype "bidirectional"))
    )
    (net (code "74") (name "unconnected-(U$3-ANT_DET-Pad62)") (class "Default")
      (node (ref "U$3") (pin "62") (pinfunction "ANT_DET_62") (pintype "bidirectional"))
    )
    (net (code "75") (name "unconnected-(U$3-DCD-Pad8)") (class "Default")
      (node (ref "U$3") (pin "8") (pinfunction "DCD_8") (pintype "bidirectional"))
    )
    (net (code "76") (name "unconnected-(U$3-DSR-Pad6)") (class "Default")
      (node (ref "U$3") (pin "6") (pinfunction "DSR_6") (pintype "bidirectional"))
    )
    (net (code "77") (name "unconnected-(U$3-GPIO5-Pad42)") (class "Default")
      (node (ref "U$3") (pin "42") (pinfunction "GPIO5_42") (pintype "bidirectional"))
    )
    (net (code "78") (name "unconnected-(U$3-GPIO6-Pad19)") (class "Default")
      (node (ref "U$3") (pin "19") (pinfunction "GPIO6_19") (pintype "bidirectional"))
    )
    (net (code "79") (name "unconnected-(U$3-I2S_CLK{slash}CLK-Pad36)") (class "Default")
      (node (ref "U$3") (pin "36") (pinfunction "I2S_CLK/CLK_36") (pintype "bidirectional"))
    )
    (net (code "80") (name "unconnected-(U$3-I2S_RXD{slash}MISO-Pad37)") (class "Default")
      (node (ref "U$3") (pin "37") (pinfunction "I2S_RXD/MISO_37") (pintype "bidirectional"))
    )
    (net (code "81") (name "unconnected-(U$3-I2S_TXD{slash}CS-Pad35)") (class "Default")
      (node (ref "U$3") (pin "35") (pinfunction "I2S_TXD/CS_35") (pintype "bidirectional"))
    )
    (net (code "82") (name "unconnected-(U$3-I2S_WA{slash}MOSI-Pad34)") (class "Default")
      (node (ref "U$3") (pin "34") (pinfunction "I2S_WA/MOSI_34") (pintype "bidirectional"))
    )
    (net (code "83") (name "unconnected-(U$3-RI-Pad7)") (class "Default")
      (node (ref "U$3") (pin "7") (pinfunction "RI_7") (pintype "bidirectional"))
    )
    (net (code "84") (name "unconnected-(U$3-SCL-Pad27)") (class "Default")
      (node (ref "U$3") (pin "27") (pinfunction "SCL_27") (pintype "bidirectional"))
    )
    (net (code "85") (name "unconnected-(U$3-SDA-Pad26)") (class "Default")
      (node (ref "U$3") (pin "26") (pinfunction "SDA_26") (pintype "bidirectional"))
    )
    (net (code "86") (name "unconnected-(U$3-SDIO_CLK-Pad45)") (class "Default")
      (node (ref "U$3") (pin "45") (pinfunction "SDIO_CLK_45") (pintype "bidirectional"))
    )
    (net (code "87") (name "unconnected-(U$3-SDIO_CMD-Pad46)") (class "Default")
      (node (ref "U$3") (pin "46") (pinfunction "SDIO_CMD_46") (pintype "bidirectional"))
    )
    (net (code "88") (name "unconnected-(U$3-SDIO_D0-Pad47)") (class "Default")
      (node (ref "U$3") (pin "47") (pinfunction "SDIO_D0_47") (pintype "bidirectional"))
    )
    (net (code "89") (name "unconnected-(U$3-SDIO_D1-Pad49)") (class "Default")
      (node (ref "U$3") (pin "49") (pinfunction "SDIO_D1_49") (pintype "bidirectional"))
    )
    (net (code "90") (name "unconnected-(U$3-SDIO_D2-Pad44)") (class "Default")
      (node (ref "U$3") (pin "44") (pinfunction "SDIO_D2_44") (pintype "bidirectional"))
    )
    (net (code "91") (name "unconnected-(U$3-SDIO_D3-Pad48)") (class "Default")
      (node (ref "U$3") (pin "48") (pinfunction "SDIO_D3_48") (pintype "bidirectional"))
    )
    (net (code "92") (name "unconnected-(U$3-V_INT-Pad4)") (class "Default")
      (node (ref "U$3") (pin "4") (pinfunction "V_INT_4") (pintype "bidirectional"))
    )
    (net (code "93") (name "unconnected-(U$5-ID-PadP$4)") (class "Default")
      (node (ref "U$5") (pin "P$4") (pinfunction "ID_P$4") (pintype "bidirectional"))
    )
    (net (code "94") (name "unconnected-(U$9-PadP$2)") (class "Default")
      (node (ref "U$9") (pin "P$2") (pinfunction "P$2_P$2") (pintype "bidirectional"))
    )
    (net (code "95") (name "unconnected-(U$9-PadP$3)") (class "Default")
      (node (ref "U$9") (pin "P$3") (pinfunction "P$3_P$3") (pintype "bidirectional"))
    )
    (net (code "96") (name "unconnected-(U$10-CT-Pad4)") (class "Default")
      (node (ref "U$10") (pin "4") (pinfunction "CT_4") (pintype "bidirectional"))
    )
    (net (code "97") (name "unconnected-(U$10-QOD-Pad5)") (class "Default")
      (node (ref "U$10") (pin "5") (pinfunction "QOD_5") (pintype "bidirectional"))
    )
    (net (code "98") (name "unconnected-(U$12-D+-PadP$3)") (class "Default")
      (node (ref "U$12") (pin "P$3") (pinfunction "D+_P$3") (pintype "bidirectional"))
    )
    (net (code "99") (name "unconnected-(U$12-D--PadP$2)") (class "Default")
      (node (ref "U$12") (pin "P$2") (pinfunction "D-_P$2") (pintype "bidirectional"))
    )
    (net (code "100") (name "unconnected-(U$12-ID-PadP$4)") (class "Default")
      (node (ref "U$12") (pin "P$4") (pinfunction "ID_P$4") (pintype "bidirectional"))
    )
    (net (code "101") (name "~{RST}") (class "Default")
      (node (ref "J1") (pin "4") (pinfunction "4_4") (pintype "passive"))
      (node (ref "U$1") (pin "4") (pinfunction "NRST_4") (pintype "bidirectional"))
    )
  )
)
